# MPPT_LCD.net
KiCad netlist of a schematic drawn in EAGLE
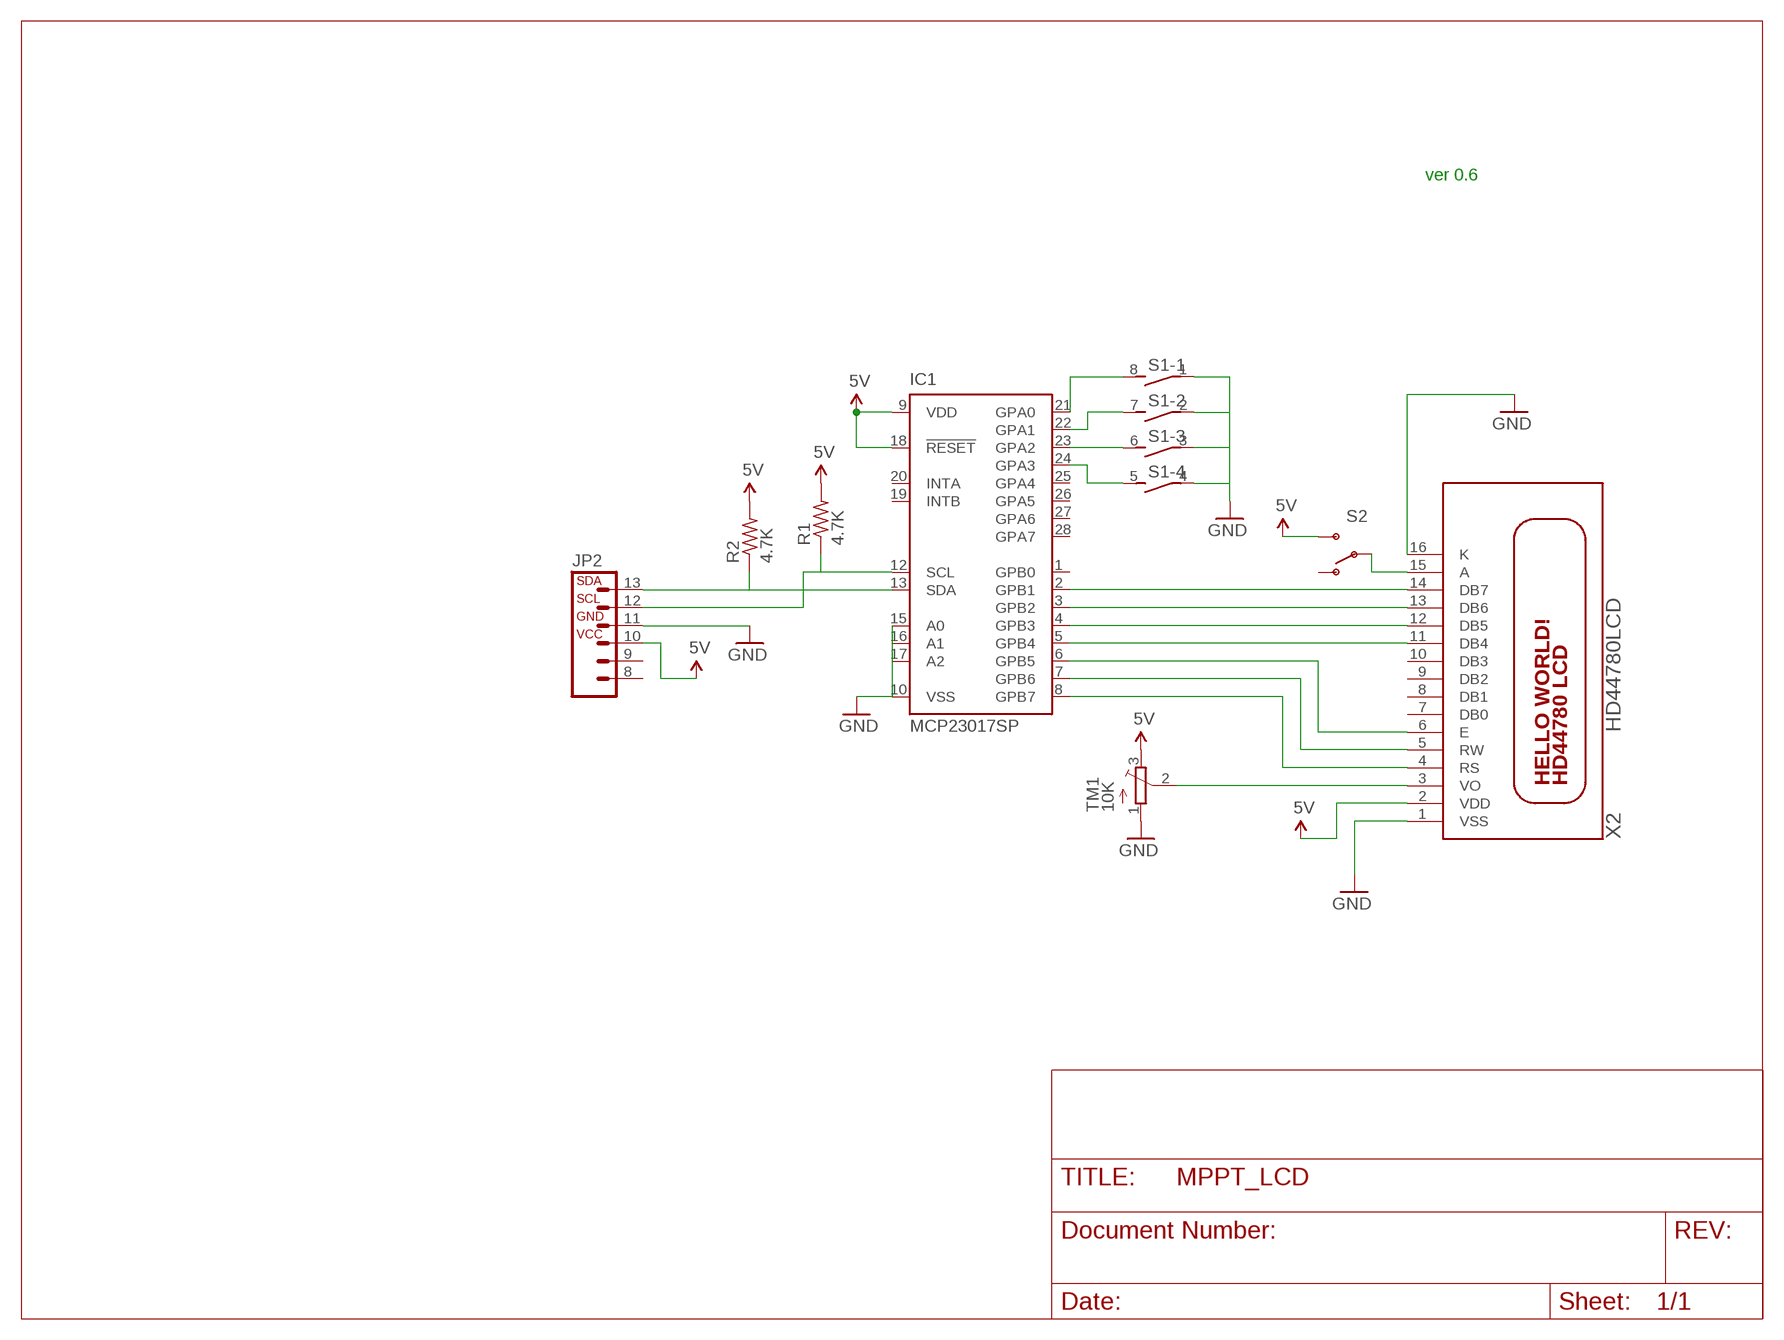
[diagram p0: schematic, sheet 1]

(export (version "E")
  (design (tool "Eeschema 10.0.6"))
  (components
    (comp (ref "IC1")
      (value "MCP23017SP")
      (footprint "eagle-import:DIL28-3")
      (libsource (lib "eagle-import") (part "MCP23017SP"))
    )
    (comp (ref "JP2")
      (value "M06_MPPT_DATA")
      (footprint "eagle-import:M06_MPPT_DATA")
      (libsource (lib "eagle-import") (part "M06_MPPT_DATA"))
    )
    (comp (ref "R1")
      (value "4.7K")
      (footprint "eagle-import:0207_10")
      (libsource (lib "eagle-import") (part "R-US_0207/10"))
    )
    (comp (ref "R2")
      (value "4.7K")
      (footprint "eagle-import:0207_10")
      (libsource (lib "eagle-import") (part "R-US_0207/10"))
    )
    (comp (ref "S1")
      (value "DIP04S")
      (footprint "eagle-import:DIP04S")
      (libsource (lib "eagle-import") (part "DIP04S"))
    )
    (comp (ref "S2")
      (value "SWITCH-SPDTPTH")
      (footprint "eagle-import:SWITCH-SPDT")
      (libsource (lib "eagle-import") (part "SWITCH-SPDTPTH"))
    )
    (comp (ref "TM1")
      (value "10K")
      (footprint "eagle-import:TRIM-3386U")
      (libsource (lib "eagle-import") (part "TRIMPOT"))
    )
    (comp (ref "X2")
      (value "HD44780LCD")
      (footprint "eagle-import:LCD_40_04")
      (libsource (lib "eagle-import") (part "HD44780LCD"))
    )
  )
  (nets
    (net (code "1") (name "5V") (class "Default")
      (node (ref "IC1") (pin "18") (pinfunction "~{RESET}_18") (pintype "input"))
      (node (ref "IC1") (pin "9") (pinfunction "VDD_9") (pintype "power_in"))
      (node (ref "JP2") (pin "10") (pinfunction "10_10") (pintype "passive"))
      (node (ref "R1") (pin "2") (pinfunction "2_2") (pintype "passive"))
      (node (ref "R2") (pin "2") (pinfunction "2_2") (pintype "passive"))
      (node (ref "S2") (pin "3") (pinfunction "S_3") (pintype "passive"))
      (node (ref "TM1") (pin "3") (pinfunction "E_3") (pintype "passive"))
      (node (ref "X2") (pin "2") (pinfunction "VDD_2") (pintype "power_in"))
    )
    (net (code "2") (name "GND") (class "Default")
      (node (ref "IC1") (pin "10") (pinfunction "VSS_10") (pintype "power_in"))
      (node (ref "IC1") (pin "15") (pinfunction "A0_15") (pintype "input"))
      (node (ref "IC1") (pin "16") (pinfunction "A1_16") (pintype "input"))
      (node (ref "IC1") (pin "17") (pinfunction "A2_17") (pintype "input"))
      (node (ref "JP2") (pin "11") (pinfunction "11_11") (pintype "passive"))
      (node (ref "S1") (pin "1") (pinfunction "1_1") (pintype "passive"))
      (node (ref "S1") (pin "2") (pinfunction "1_2") (pintype "passive"))
      (node (ref "S1") (pin "3") (pinfunction "1_3") (pintype "passive"))
      (node (ref "S1") (pin "4") (pinfunction "1_4") (pintype "passive"))
      (node (ref "TM1") (pin "1") (pinfunction "A_1") (pintype "passive"))
      (node (ref "X2") (pin "1") (pinfunction "VSS_1") (pintype "power_in"))
      (node (ref "X2") (pin "16") (pinfunction "K_16") (pintype "input"))
    )
    (net (code "3") (name "Net-(IC1-GPA0)") (class "Default")
      (node (ref "IC1") (pin "21") (pinfunction "GPA0_21") (pintype "bidirectional"))
      (node (ref "S1") (pin "8") (pinfunction "2_8") (pintype "passive"))
    )
    (net (code "4") (name "Net-(IC1-GPA1)") (class "Default")
      (node (ref "IC1") (pin "22") (pinfunction "GPA1_22") (pintype "bidirectional"))
      (node (ref "S1") (pin "7") (pinfunction "2_7") (pintype "passive"))
    )
    (net (code "5") (name "Net-(IC1-GPA2)") (class "Default")
      (node (ref "IC1") (pin "23") (pinfunction "GPA2_23") (pintype "bidirectional"))
      (node (ref "S1") (pin "6") (pinfunction "2_6") (pintype "passive"))
    )
    (net (code "6") (name "Net-(IC1-GPA3)") (class "Default")
      (node (ref "IC1") (pin "24") (pinfunction "GPA3_24") (pintype "bidirectional"))
      (node (ref "S1") (pin "5") (pinfunction "2_5") (pintype "passive"))
    )
    (net (code "7") (name "Net-(IC1-GPB1)") (class "Default")
      (node (ref "IC1") (pin "2") (pinfunction "GPB1_2") (pintype "bidirectional"))
      (node (ref "X2") (pin "14") (pinfunction "DB7_14") (pintype "bidirectional"))
    )
    (net (code "8") (name "Net-(IC1-GPB2)") (class "Default")
      (node (ref "IC1") (pin "3") (pinfunction "GPB2_3") (pintype "bidirectional"))
      (node (ref "X2") (pin "13") (pinfunction "DB6_13") (pintype "bidirectional"))
    )
    (net (code "9") (name "Net-(IC1-GPB3)") (class "Default")
      (node (ref "IC1") (pin "4") (pinfunction "GPB3_4") (pintype "bidirectional"))
      (node (ref "X2") (pin "12") (pinfunction "DB5_12") (pintype "bidirectional"))
    )
    (net (code "10") (name "Net-(IC1-GPB4)") (class "Default")
      (node (ref "IC1") (pin "5") (pinfunction "GPB4_5") (pintype "bidirectional"))
      (node (ref "X2") (pin "11") (pinfunction "DB4_11") (pintype "bidirectional"))
    )
    (net (code "11") (name "Net-(IC1-GPB5)") (class "Default")
      (node (ref "IC1") (pin "6") (pinfunction "GPB5_6") (pintype "bidirectional"))
      (node (ref "X2") (pin "6") (pinfunction "E_6") (pintype "input"))
    )
    (net (code "12") (name "Net-(IC1-GPB6)") (class "Default")
      (node (ref "IC1") (pin "7") (pinfunction "GPB6_7") (pintype "bidirectional"))
      (node (ref "X2") (pin "5") (pinfunction "RW_5") (pintype "input"))
    )
    (net (code "13") (name "Net-(IC1-GPB7)") (class "Default")
      (node (ref "IC1") (pin "8") (pinfunction "GPB7_8") (pintype "bidirectional"))
      (node (ref "X2") (pin "4") (pinfunction "RS_4") (pintype "input"))
    )
    (net (code "14") (name "Net-(IC1-SCL)") (class "Default")
      (node (ref "IC1") (pin "12") (pinfunction "SCL_12") (pintype "input"))
      (node (ref "JP2") (pin "12") (pinfunction "12_12") (pintype "passive"))
      (node (ref "R1") (pin "1") (pinfunction "1_1") (pintype "passive"))
    )
    (net (code "15") (name "Net-(IC1-SDA)") (class "Default")
      (node (ref "IC1") (pin "13") (pinfunction "SDA_13") (pintype "bidirectional"))
      (node (ref "JP2") (pin "13") (pinfunction "13_13") (pintype "passive"))
      (node (ref "R2") (pin "1") (pinfunction "1_1") (pintype "passive"))
    )
    (net (code "16") (name "Net-(S2-P)") (class "Default")
      (node (ref "S2") (pin "2") (pinfunction "P_2") (pintype "passive"))
      (node (ref "X2") (pin "15") (pinfunction "A_15") (pintype "input"))
    )
    (net (code "17") (name "Net-(TM1-S)") (class "Default")
      (node (ref "TM1") (pin "2") (pinfunction "S_2") (pintype "passive"))
      (node (ref "X2") (pin "3") (pinfunction "VO_3") (pintype "input"))
    )
    (net (code "18") (name "unconnected-(IC1-GPA4-Pad25)") (class "Default")
      (node (ref "IC1") (pin "25") (pinfunction "GPA4_25") (pintype "bidirectional"))
    )
    (net (code "19") (name "unconnected-(IC1-GPA5-Pad26)") (class "Default")
      (node (ref "IC1") (pin "26") (pinfunction "GPA5_26") (pintype "bidirectional"))
    )
    (net (code "20") (name "unconnected-(IC1-GPA6-Pad27)") (class "Default")
      (node (ref "IC1") (pin "27") (pinfunction "GPA6_27") (pintype "bidirectional"))
    )
    (net (code "21") (name "unconnected-(IC1-GPA7-Pad28)") (class "Default")
      (node (ref "IC1") (pin "28") (pinfunction "GPA7_28") (pintype "bidirectional"))
    )
    (net (code "22") (name "unconnected-(IC1-GPB0-Pad1)") (class "Default")
      (node (ref "IC1") (pin "1") (pinfunction "GPB0_1") (pintype "bidirectional"))
    )
    (net (code "23") (name "unconnected-(IC1-INTA-Pad20)") (class "Default")
      (node (ref "IC1") (pin "20") (pinfunction "INTA_20") (pintype "output"))
    )
    (net (code "24") (name "unconnected-(IC1-INTB-Pad19)") (class "Default")
      (node (ref "IC1") (pin "19") (pinfunction "INTB_19") (pintype "output"))
    )
    (net (code "25") (name "unconnected-(JP2-Pad8)") (class "Default")
      (node (ref "JP2") (pin "8") (pinfunction "8_8") (pintype "passive"))
    )
    (net (code "26") (name "unconnected-(JP2-Pad9)") (class "Default")
      (node (ref "JP2") (pin "9") (pinfunction "9_9") (pintype "passive"))
    )
    (net (code "27") (name "unconnected-(S2-O-Pad1)") (class "Default")
      (node (ref "S2") (pin "1") (pinfunction "O_1") (pintype "passive"))
    )
    (net (code "28") (name "unconnected-(X2-DB0-Pad7)") (class "Default")
      (node (ref "X2") (pin "7") (pinfunction "DB0_7") (pintype "bidirectional"))
    )
    (net (code "29") (name "unconnected-(X2-DB1-Pad8)") (class "Default")
      (node (ref "X2") (pin "8") (pinfunction "DB1_8") (pintype "bidirectional"))
    )
    (net (code "30") (name "unconnected-(X2-DB2-Pad9)") (class "Default")
      (node (ref "X2") (pin "9") (pinfunction "DB2_9") (pintype "bidirectional"))
    )
    (net (code "31") (name "unconnected-(X2-DB3-Pad10)") (class "Default")
      (node (ref "X2") (pin "10") (pinfunction "DB3_10") (pintype "bidirectional"))
    )
  )
)
